# BUTTON_N_ADCREAD.net
KiCad netlist of a schematic drawn in Altium Designer
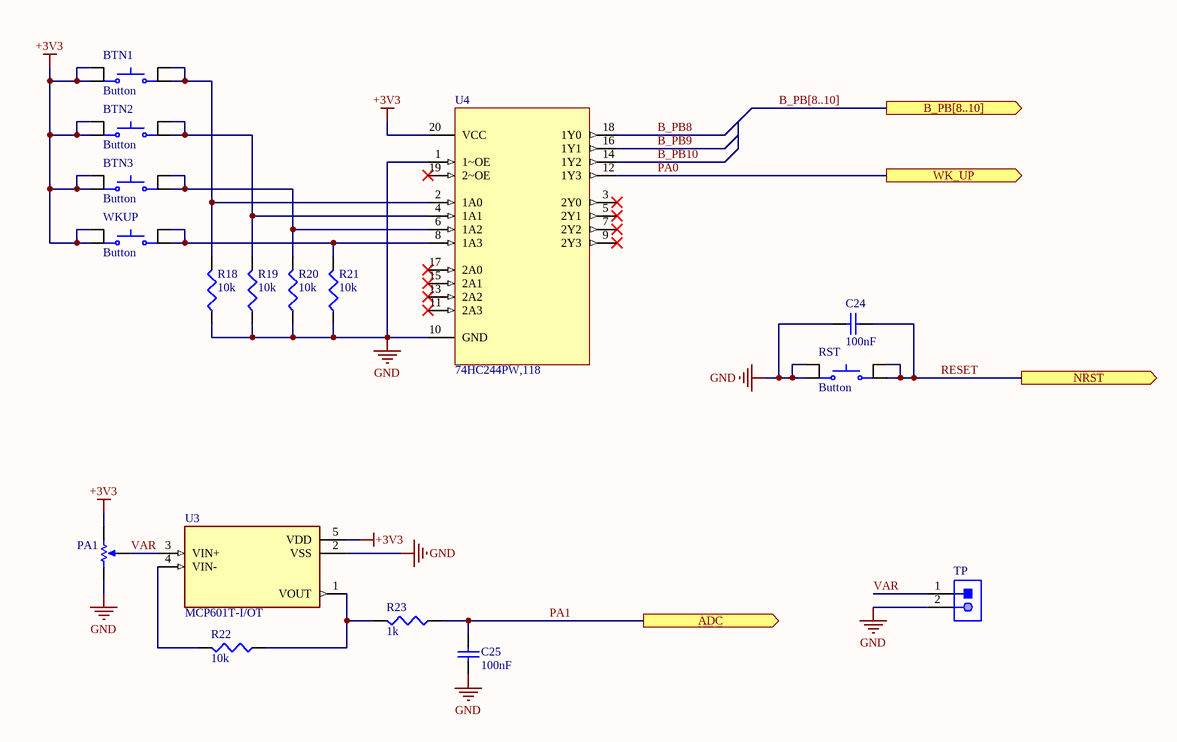
[diagram p0: BUTTON_N_ADCREAD.SchDoc]

(export (version "E")
  (design (tool "Eeschema 10.0.6"))
  (components
    (comp (ref "BTN1")
      (value "Button")
      (footprint "SW_1571563-7")
      (description "Switch Tactile OFF (ON) SPST Round Button Gull Wing 0.05A 24VDC 1VA 0.98N SMD Loose")
      (fields (field (name "MF") "TE Connectivity") (field (name "MP") "1571563-7"))
      (libsource (lib "Ho Chi Minh City University of Technology") (part "Button"))
    )
    (comp (ref "BTN2")
      (value "Button")
      (footprint "SW_1571563-7")
      (description "Switch Tactile OFF (ON) SPST Round Button Gull Wing 0.05A 24VDC 1VA 0.98N SMD Loose")
      (fields (field (name "MF") "TE Connectivity") (field (name "MP") "1571563-7"))
      (libsource (lib "Ho Chi Minh City University of Technology") (part "Button"))
    )
    (comp (ref "BTN3")
      (value "Button")
      (footprint "SW_1571563-7")
      (description "Switch Tactile OFF (ON) SPST Round Button Gull Wing 0.05A 24VDC 1VA 0.98N SMD Loose")
      (fields (field (name "MF") "TE Connectivity") (field (name "MP") "1571563-7"))
      (libsource (lib "Ho Chi Minh City University of Technology") (part "Button"))
    )
    (comp (ref "C24")
      (value "100nF")
      (footprint "CAPC0805(2012)145_L")
      (description "Chip Capacitor, 100nF +/-40%, 16V, 0805, Thickness 1.45 mm")
      (fields (field (name "TOLERANCE") "5%"))
      (libsource (lib "Ho Chi Minh City University of Technology") (part "CAP-NP-2"))
    )
    (comp (ref "C25")
      (value "100nF")
      (footprint "CAPC0805(2012)145_L")
      (description "Chip Capacitor, 100nF +/-40%, 16V, 0805, Thickness 1.45 mm")
      (fields (field (name "TOLERANCE") "5%"))
      (libsource (lib "Ho Chi Minh City University of Technology") (part "CAP-NP-2"))
    )
    (comp (ref "PA1")
      (value "3362P-1-104LF")
      (footprint "BOUR-3362P")
      (fields
        (field (name "MANUFACTURER") "Bourns")
        (field (name "POWER") "500mW")
        (field (name "TOLERANCE") "10%")
      )
      (libsource (lib "Ho Chi Minh City University of Technology") (part "RES-POT-3"))
    )
    (comp (ref "R18")
      (value "10k")
      (footprint "0805 (2012 Metric)")
      (description "Oreki")
      (libsource (lib "Ho Chi Minh City University of Technology") (part "RES-2"))
    )
    (comp (ref "R19")
      (value "10k")
      (footprint "0805 (2012 Metric)")
      (description "Oreki")
      (libsource (lib "Ho Chi Minh City University of Technology") (part "RES-2"))
    )
    (comp (ref "R20")
      (value "10k")
      (footprint "0805 (2012 Metric)")
      (description "Oreki")
      (libsource (lib "Ho Chi Minh City University of Technology") (part "RES-2"))
    )
    (comp (ref "R21")
      (value "10k")
      (footprint "0805 (2012 Metric)")
      (description "Oreki")
      (libsource (lib "Ho Chi Minh City University of Technology") (part "RES-2"))
    )
    (comp (ref "R22")
      (value "10k")
      (footprint "0805 (2012 Metric)")
      (description "Oreki")
      (libsource (lib "Ho Chi Minh City University of Technology") (part "RES-2"))
    )
    (comp (ref "R23")
      (value "1k")
      (footprint "0805 (2012 Metric)")
      (description "Oreki")
      (fields (field (name "Comment") "10k"))
      (libsource (lib "Ho Chi Minh City University of Technology") (part "RES-2"))
    )
    (comp (ref "RST")
      (value "Button")
      (footprint "SW_1571563-7")
      (description "Switch Tactile OFF (ON) SPST Round Button Gull Wing 0.05A 24VDC 1VA 0.98N SMD Loose")
      (fields (field (name "MF") "TE Connectivity") (field (name "MP") "1571563-7"))
      (libsource (lib "Ho Chi Minh City University of Technology") (part "Button"))
    )
    (comp (ref "TP")
      (value "B2P-VH(LF)(SN)")
      (footprint "JST-B2P-VH(LF)(SN)_V")
      (fields (field (name "MANUFACTURER") "JST"))
      (libsource (lib "Ho Chi Minh City University of Technology") (part "CN-1P-M-R2"))
    )
    (comp (ref "U3")
      (value "MCP601T-I/OT")
      (footprint "SOT95P280X145-5N")
      (description "General Purpose Amplifier 1 Circuit Rail-to-Rail SOT-23-5")
      (fields (field (name "MF") "Microchip") (field (name "JLCPCB PART #") "C128440"))
      (libsource (lib "Ho Chi Minh City University of Technology") (part "MCP601T-I/OT"))
    )
    (comp (ref "U4")
      (value "74HC244PW,118")
      (footprint "TSSOP-20")
      (description "4 7.8mA 2V~6V 7.8mA 2 TSSOP-20  Buffer/Driver/Transceiver ROHS")
      (fields (field (name "MP") "altium_native_batch") (field (name "JLCPCB PART #") "C5623"))
      (libsource (lib "Ho Chi Minh City University of Technology") (part "74HC244PW,118"))
    )
    (comp (ref "WKUP")
      (value "Button")
      (footprint "SW_1571563-7")
      (description "Switch Tactile OFF (ON) SPST Round Button Gull Wing 0.05A 24VDC 1VA 0.98N SMD Loose")
      (fields (field (name "MF") "TE Connectivity") (field (name "MP") "1571563-7"))
      (libsource (lib "Ho Chi Minh City University of Technology") (part "Button"))
    )
  )
  (nets
    (net (code "1") (name "+3V3") (class "Default")
      (node (ref "BTN1") (pin "1") (pinfunction "COM_1") (pintype "passive"))
      (node (ref "BTN1") (pin "2") (pinfunction "COM_2") (pintype "passive"))
      (node (ref "BTN2") (pin "1") (pinfunction "COM_1") (pintype "passive"))
      (node (ref "BTN2") (pin "2") (pinfunction "COM_2") (pintype "passive"))
      (node (ref "BTN3") (pin "1") (pinfunction "COM_1") (pintype "passive"))
      (node (ref "BTN3") (pin "2") (pinfunction "COM_2") (pintype "passive"))
      (node (ref "PA1") (pin "3") (pinfunction "CW_3") (pintype "passive"))
      (node (ref "U3") (pin "5") (pinfunction "VDD_5") (pintype "power_in"))
      (node (ref "U4") (pin "20") (pinfunction "VCC_20") (pintype "power_in"))
      (node (ref "WKUP") (pin "1") (pinfunction "COM_1") (pintype "passive"))
      (node (ref "WKUP") (pin "2") (pinfunction "COM_2") (pintype "passive"))
    )
    (net (code "2") (name "/B_PB8") (class "Default")
      (node (ref "U4") (pin "18") (pinfunction "1Y0_18") (pintype "output"))
    )
    (net (code "3") (name "/B_PB9") (class "Default")
      (node (ref "U4") (pin "16") (pinfunction "1Y1_16") (pintype "output"))
    )
    (net (code "4") (name "/B_PB10") (class "Default")
      (node (ref "U4") (pin "14") (pinfunction "1Y2_14") (pintype "output"))
    )
    (net (code "6") (name "/PA0") (class "Default")
      (node (ref "U4") (pin "12") (pinfunction "1Y3_12") (pintype "output"))
    )
    (net (code "7") (name "/PA1") (class "Default")
      (node (ref "C25") (pin "2") (pinfunction "2_2") (pintype "passive"))
      (node (ref "R23") (pin "1") (pinfunction "1_1") (pintype "passive"))
    )
    (net (code "8") (name "/RESET") (class "Default")
      (node (ref "C24") (pin "1") (pinfunction "1_1") (pintype "passive"))
      (node (ref "RST") (pin "3") (pinfunction "NO_3") (pintype "passive"))
      (node (ref "RST") (pin "4") (pinfunction "NO_4") (pintype "passive"))
    )
    (net (code "9") (name "/VAR") (class "Default")
      (node (ref "PA1") (pin "2") (pinfunction "S_2") (pintype "passive"))
      (node (ref "TP") (pin "1") (pinfunction "1_1") (pintype "passive"))
      (node (ref "U3") (pin "3") (pinfunction "VIN+_3") (pintype "input"))
    )
    (net (code "10") (name "GND") (class "Default")
      (node (ref "C24") (pin "2") (pinfunction "2_2") (pintype "passive"))
      (node (ref "C25") (pin "1") (pinfunction "1_1") (pintype "passive"))
      (node (ref "PA1") (pin "1") (pinfunction "CCW_1") (pintype "passive"))
      (node (ref "R18") (pin "1") (pinfunction "1_1") (pintype "passive"))
      (node (ref "R19") (pin "1") (pinfunction "1_1") (pintype "passive"))
      (node (ref "R20") (pin "1") (pinfunction "1_1") (pintype "passive"))
      (node (ref "R21") (pin "1") (pinfunction "1_1") (pintype "passive"))
      (node (ref "RST") (pin "1") (pinfunction "COM_1") (pintype "passive"))
      (node (ref "RST") (pin "2") (pinfunction "COM_2") (pintype "passive"))
      (node (ref "TP") (pin "2") (pinfunction "2_2") (pintype "passive"))
      (node (ref "U3") (pin "2") (pinfunction "VSS_2") (pintype "power_in"))
      (node (ref "U4") (pin "1") (pinfunction "1~OE_1") (pintype "input"))
      (node (ref "U4") (pin "10") (pinfunction "GND_10") (pintype "passive"))
    )
    (net (code "11") (name "Net-(U3-VIN-)") (class "Default")
      (node (ref "R22") (pin "2") (pinfunction "2_2") (pintype "passive"))
      (node (ref "U3") (pin "4") (pinfunction "VIN-_4") (pintype "input"))
    )
    (net (code "12") (name "Net-(U3-VOUT)") (class "Default")
      (node (ref "R22") (pin "1") (pinfunction "1_1") (pintype "passive"))
      (node (ref "R23") (pin "2") (pinfunction "2_2") (pintype "passive"))
      (node (ref "U3") (pin "1") (pinfunction "VOUT_1") (pintype "output"))
    )
    (net (code "13") (name "Net-(U4-1A0)") (class "Default")
      (node (ref "BTN1") (pin "3") (pinfunction "NO_3") (pintype "passive"))
      (node (ref "BTN1") (pin "4") (pinfunction "NO_4") (pintype "passive"))
      (node (ref "R18") (pin "2") (pinfunction "2_2") (pintype "passive"))
      (node (ref "U4") (pin "2") (pinfunction "1A0_2") (pintype "input"))
    )
    (net (code "14") (name "Net-(U4-1A1)") (class "Default")
      (node (ref "BTN2") (pin "3") (pinfunction "NO_3") (pintype "passive"))
      (node (ref "BTN2") (pin "4") (pinfunction "NO_4") (pintype "passive"))
      (node (ref "R19") (pin "2") (pinfunction "2_2") (pintype "passive"))
      (node (ref "U4") (pin "4") (pinfunction "1A1_4") (pintype "input"))
    )
    (net (code "15") (name "Net-(U4-1A2)") (class "Default")
      (node (ref "BTN3") (pin "3") (pinfunction "NO_3") (pintype "passive"))
      (node (ref "BTN3") (pin "4") (pinfunction "NO_4") (pintype "passive"))
      (node (ref "R20") (pin "2") (pinfunction "2_2") (pintype "passive"))
      (node (ref "U4") (pin "6") (pinfunction "1A2_6") (pintype "input"))
    )
    (net (code "16") (name "Net-(U4-1A3)") (class "Default")
      (node (ref "R21") (pin "2") (pinfunction "2_2") (pintype "passive"))
      (node (ref "U4") (pin "8") (pinfunction "1A3_8") (pintype "input"))
      (node (ref "WKUP") (pin "3") (pinfunction "NO_3") (pintype "passive"))
      (node (ref "WKUP") (pin "4") (pinfunction "NO_4") (pintype "passive"))
    )
    (net (code "17") (name "unconnected-(U4-2A0-Pad17)") (class "Default")
      (node (ref "U4") (pin "17") (pinfunction "2A0_17") (pintype "input+no_connect"))
    )
    (net (code "18") (name "unconnected-(U4-2A1-Pad15)") (class "Default")
      (node (ref "U4") (pin "15") (pinfunction "2A1_15") (pintype "input+no_connect"))
    )
    (net (code "19") (name "unconnected-(U4-2A2-Pad13)") (class "Default")
      (node (ref "U4") (pin "13") (pinfunction "2A2_13") (pintype "input+no_connect"))
    )
    (net (code "20") (name "unconnected-(U4-2A3-Pad11)") (class "Default")
      (node (ref "U4") (pin "11") (pinfunction "2A3_11") (pintype "input+no_connect"))
    )
    (net (code "21") (name "unconnected-(U4-2Y0-Pad3)") (class "Default")
      (node (ref "U4") (pin "3") (pinfunction "2Y0_3") (pintype "output+no_connect"))
    )
    (net (code "22") (name "unconnected-(U4-2Y1-Pad5)") (class "Default")
      (node (ref "U4") (pin "5") (pinfunction "2Y1_5") (pintype "output+no_connect"))
    )
    (net (code "23") (name "unconnected-(U4-2Y2-Pad7)") (class "Default")
      (node (ref "U4") (pin "7") (pinfunction "2Y2_7") (pintype "output+no_connect"))
    )
    (net (code "24") (name "unconnected-(U4-2Y3-Pad9)") (class "Default")
      (node (ref "U4") (pin "9") (pinfunction "2Y3_9") (pintype "output+no_connect"))
    )
    (net (code "25") (name "unconnected-(U4-2~OE-Pad19)") (class "Default")
      (node (ref "U4") (pin "19") (pinfunction "2~OE_19") (pintype "input+no_connect"))
    )
  )
)
